# ESP8266_usb_spi_connector3.net
KiCad netlist of a schematic drawn in EAGLE
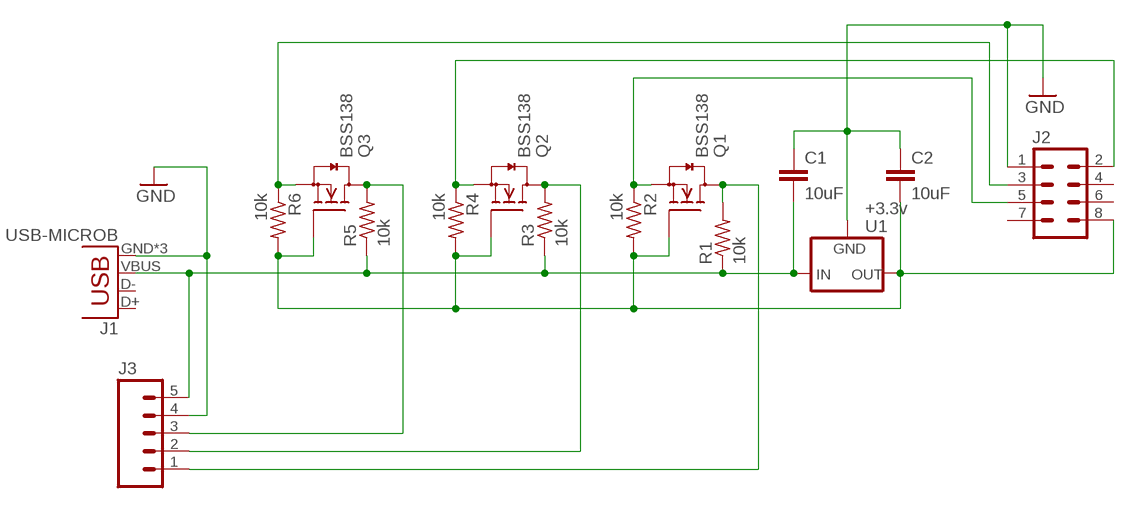
[diagram p0: schematic, sheet 1]

(export (version "E")
  (design (tool "Eeschema 10.0.6"))
  (components
    (comp (ref "C1")
      (value "10uF")
      (footprint "eagle-import:1206")
      (libsource (lib "eagle-import") (part "CAP1206"))
    )
    (comp (ref "C2")
      (value "10uF")
      (footprint "eagle-import:1206")
      (libsource (lib "eagle-import") (part "CAP1206"))
    )
    (comp (ref "J1")
      (value "USB-MICROB")
      (footprint "eagle-import:USB-MICROB")
      (libsource (lib "eagle-import") (part "USB-MICROB"))
    )
    (comp (ref "J2")
      (value "M04X2")
      (footprint "eagle-import:2X4")
      (libsource (lib "eagle-import") (part "M04X2"))
    )
    (comp (ref "J3")
      (value "M05PTH")
      (footprint "eagle-import:1X05")
      (libsource (lib "eagle-import") (part "M05PTH"))
    )
    (comp (ref "Q1")
      (value "BSS138")
      (footprint "eagle-import:SOT23")
      (libsource (lib "eagle-import") (part "BSS138"))
    )
    (comp (ref "Q2")
      (value "BSS138")
      (footprint "eagle-import:SOT23")
      (libsource (lib "eagle-import") (part "BSS138"))
    )
    (comp (ref "Q3")
      (value "BSS138")
      (footprint "eagle-import:SOT23")
      (libsource (lib "eagle-import") (part "BSS138"))
    )
    (comp (ref "R1")
      (value "10k")
      (footprint "eagle-import:M1206")
      (libsource (lib "eagle-import") (part "R-US_M1206"))
    )
    (comp (ref "R2")
      (value "10k")
      (footprint "eagle-import:M1206")
      (libsource (lib "eagle-import") (part "R-US_M1206"))
    )
    (comp (ref "R3")
      (value "10k")
      (footprint "eagle-import:M1206")
      (libsource (lib "eagle-import") (part "R-US_M1206"))
    )
    (comp (ref "R4")
      (value "10k")
      (footprint "eagle-import:M1206")
      (libsource (lib "eagle-import") (part "R-US_M1206"))
    )
    (comp (ref "R5")
      (value "10k")
      (footprint "eagle-import:M1206")
      (libsource (lib "eagle-import") (part "R-US_M1206"))
    )
    (comp (ref "R6")
      (value "10k")
      (footprint "eagle-import:M1206")
      (libsource (lib "eagle-import") (part "R-US_M1206"))
    )
    (comp (ref "U1")
      (value "+3.3v")
      (footprint "eagle-import:TO-252")
      (libsource (lib "eagle-import") (part "V_REG_78XX7812"))
    )
  )
  (nets
    (net (code "1") (name "GND") (class "Default")
      (node (ref "C1") (pin "1") (pinfunction "1_1") (pintype "passive"))
      (node (ref "C2") (pin "1") (pinfunction "1_1") (pintype "passive"))
      (node (ref "J1") (pin "GND") (pinfunction "GND_GND") (pintype "bidirectional"))
      (node (ref "J1") (pin "MT1") (pinfunction "GND_MT1") (pintype "bidirectional"))
      (node (ref "J1") (pin "MT2") (pinfunction "GND_MT2") (pintype "bidirectional"))
      (node (ref "J2") (pin "1") (pinfunction "1_1") (pintype "passive"))
      (node (ref "J3") (pin "4") (pinfunction "4_4") (pintype "passive"))
      (node (ref "U1") (pin "3") (pinfunction "GND_3") (pintype "input"))
    )
    (net (code "2") (name "Net-(Q1-D)") (class "Default")
      (node (ref "J3") (pin "1") (pinfunction "1_1") (pintype "passive"))
      (node (ref "Q1") (pin "3") (pinfunction "D_3") (pintype "passive"))
      (node (ref "R1") (pin "2") (pinfunction "2_2") (pintype "passive"))
    )
    (net (code "3") (name "Net-(Q1-G)") (class "Default")
      (node (ref "C2") (pin "2") (pinfunction "2_2") (pintype "passive"))
      (node (ref "J2") (pin "8") (pinfunction "8_8") (pintype "passive"))
      (node (ref "Q1") (pin "1") (pinfunction "G_1") (pintype "passive"))
      (node (ref "Q2") (pin "1") (pinfunction "G_1") (pintype "passive"))
      (node (ref "Q3") (pin "1") (pinfunction "G_1") (pintype "passive"))
      (node (ref "R2") (pin "2") (pinfunction "2_2") (pintype "passive"))
      (node (ref "R4") (pin "2") (pinfunction "2_2") (pintype "passive"))
      (node (ref "R6") (pin "2") (pinfunction "2_2") (pintype "passive"))
      (node (ref "U1") (pin "2") (pinfunction "OUT_2") (pintype "passive"))
    )
    (net (code "4") (name "Net-(Q1-S)") (class "Default")
      (node (ref "J2") (pin "5") (pinfunction "5_5") (pintype "passive"))
      (node (ref "Q1") (pin "2") (pinfunction "S_2") (pintype "passive"))
      (node (ref "R2") (pin "1") (pinfunction "1_1") (pintype "passive"))
    )
    (net (code "5") (name "Net-(Q2-D)") (class "Default")
      (node (ref "J3") (pin "2") (pinfunction "2_2") (pintype "passive"))
      (node (ref "Q2") (pin "3") (pinfunction "D_3") (pintype "passive"))
      (node (ref "R3") (pin "2") (pinfunction "2_2") (pintype "passive"))
    )
    (net (code "6") (name "Net-(Q2-S)") (class "Default")
      (node (ref "J2") (pin "2") (pinfunction "2_2") (pintype "passive"))
      (node (ref "Q2") (pin "2") (pinfunction "S_2") (pintype "passive"))
      (node (ref "R4") (pin "1") (pinfunction "1_1") (pintype "passive"))
    )
    (net (code "7") (name "Net-(Q3-D)") (class "Default")
      (node (ref "J3") (pin "3") (pinfunction "3_3") (pintype "passive"))
      (node (ref "Q3") (pin "3") (pinfunction "D_3") (pintype "passive"))
      (node (ref "R5") (pin "2") (pinfunction "2_2") (pintype "passive"))
    )
    (net (code "8") (name "Net-(Q3-S)") (class "Default")
      (node (ref "J2") (pin "3") (pinfunction "3_3") (pintype "passive"))
      (node (ref "Q3") (pin "2") (pinfunction "S_2") (pintype "passive"))
      (node (ref "R6") (pin "1") (pinfunction "1_1") (pintype "passive"))
    )
    (net (code "9") (name "Net-(U1-IN)") (class "Default")
      (node (ref "C1") (pin "2") (pinfunction "2_2") (pintype "passive"))
      (node (ref "J1") (pin "VBUS") (pinfunction "VBUS_VBUS") (pintype "bidirectional"))
      (node (ref "J3") (pin "5") (pinfunction "5_5") (pintype "passive"))
      (node (ref "R1") (pin "1") (pinfunction "1_1") (pintype "passive"))
      (node (ref "R3") (pin "1") (pinfunction "1_1") (pintype "passive"))
      (node (ref "R5") (pin "1") (pinfunction "1_1") (pintype "passive"))
      (node (ref "U1") (pin "1") (pinfunction "IN_1") (pintype "input"))
    )
    (net (code "10") (name "unconnected-(J1-PadD+)") (class "Default")
      (node (ref "J1") (pin "D+") (pinfunction "D+_D+") (pintype "bidirectional"))
    )
    (net (code "11") (name "unconnected-(J1-PadD-)") (class "Default")
      (node (ref "J1") (pin "D-") (pinfunction "D-_D-") (pintype "bidirectional"))
    )
    (net (code "12") (name "unconnected-(J2-Pad4)") (class "Default")
      (node (ref "J2") (pin "4") (pinfunction "4_4") (pintype "passive"))
    )
    (net (code "13") (name "unconnected-(J2-Pad6)") (class "Default")
      (node (ref "J2") (pin "6") (pinfunction "6_6") (pintype "passive"))
    )
    (net (code "14") (name "unconnected-(J2-Pad7)") (class "Default")
      (node (ref "J2") (pin "7") (pinfunction "7_7") (pintype "passive"))
    )
  )
)
